# W700B.net
KiCad netlist of a schematic drawn in EAGLE
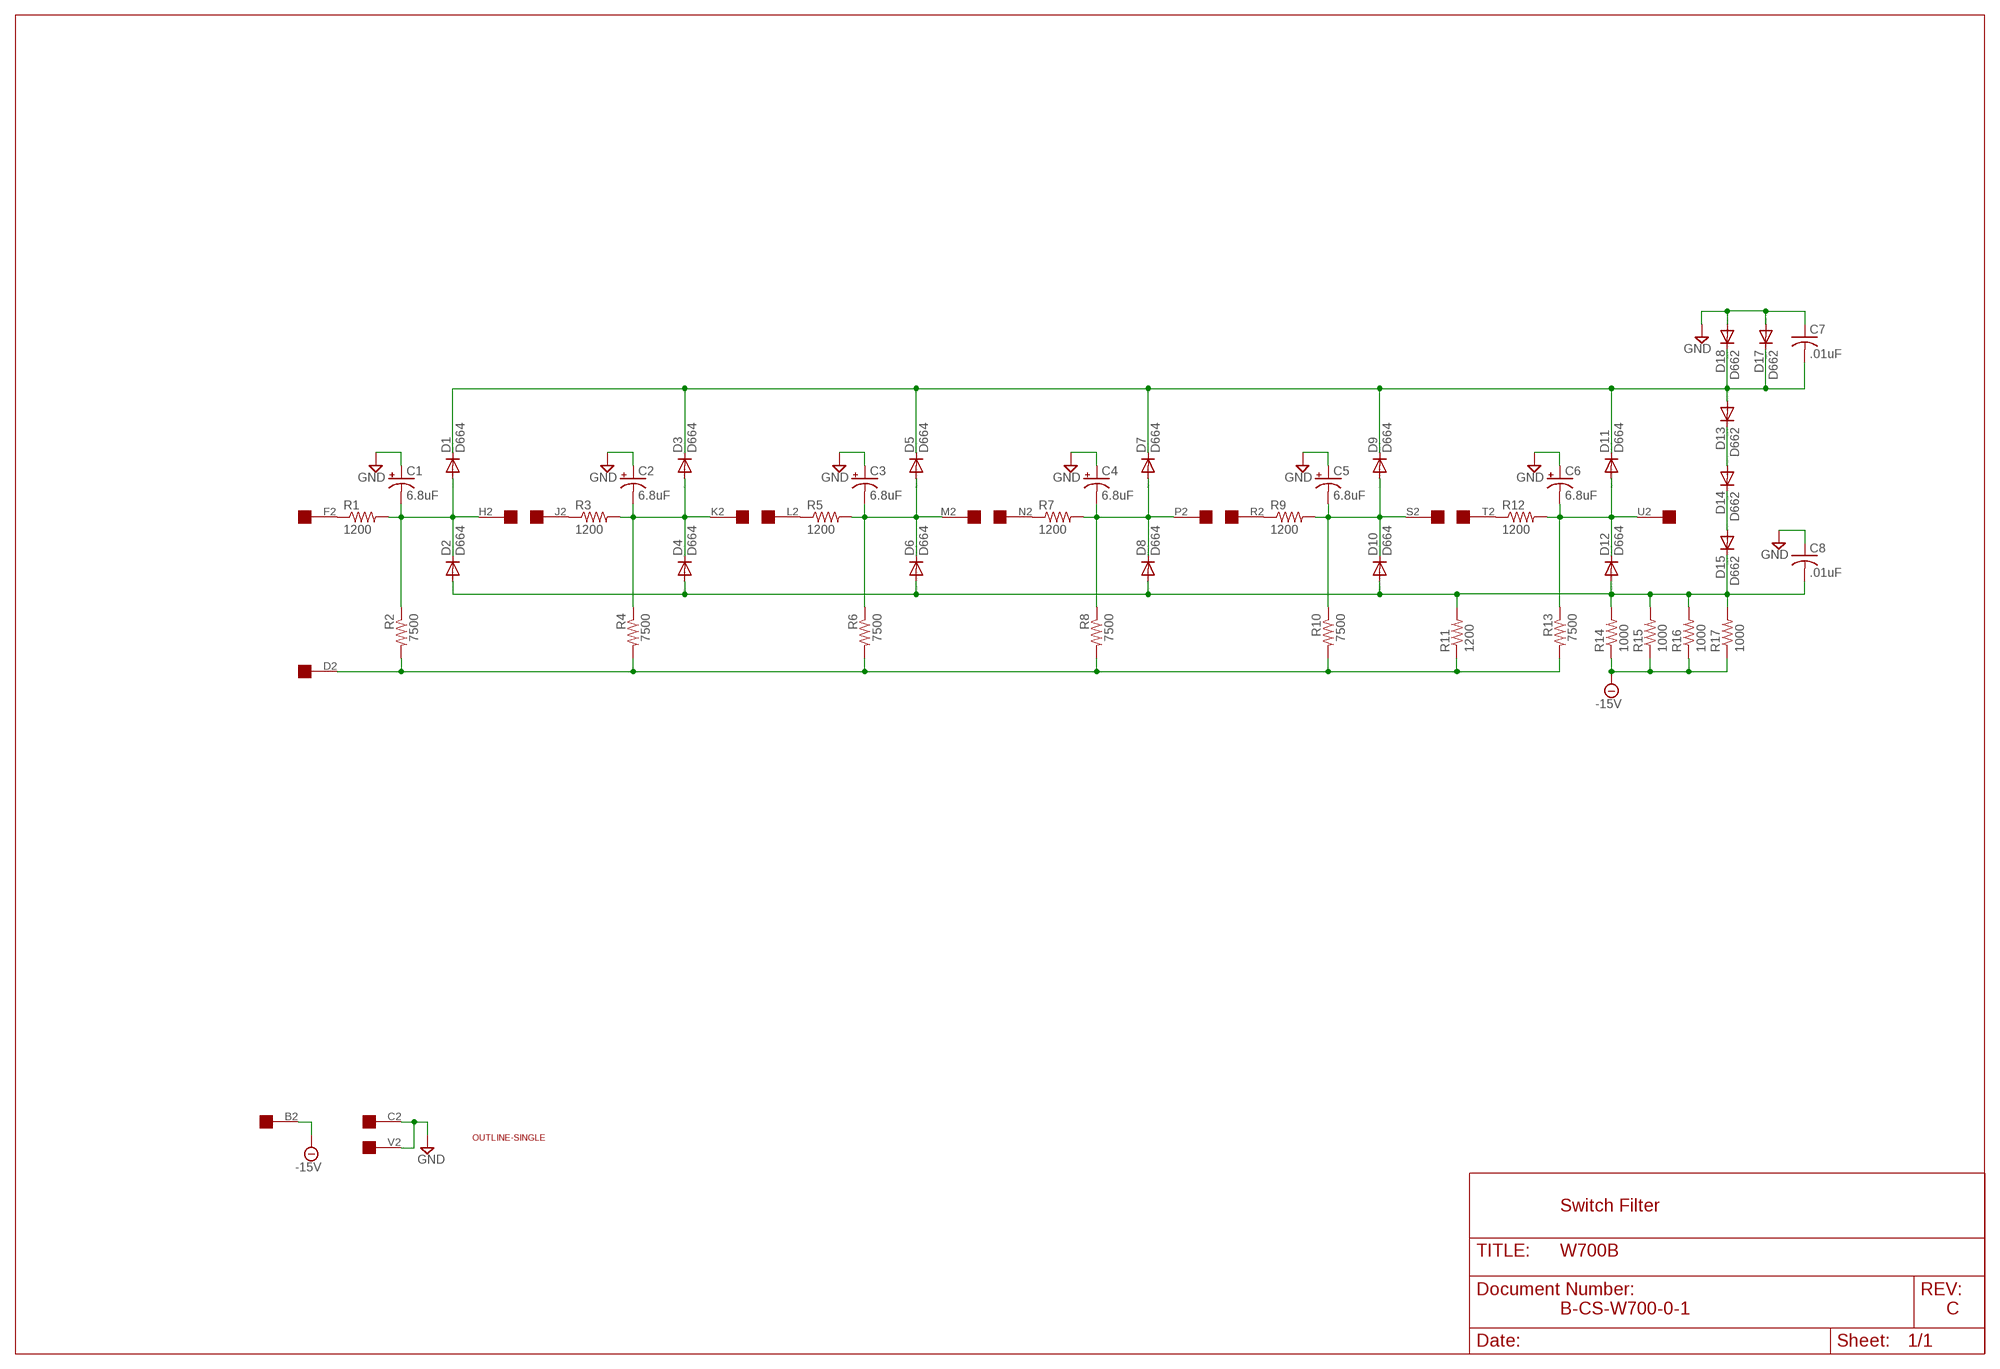
[diagram p0: schematic, sheet 1]

(export (version "E")
  (design (tool "Eeschema 10.0.6"))
  (components
    (comp (ref "C1")
      (value "6.8uF")
      (footprint "eagle-import:E12-8")
      (libsource (lib "eagle-import") (part "CPOL-USE20-8AXIAL"))
    )
    (comp (ref "C2")
      (value "6.8uF")
      (footprint "eagle-import:E12-8")
      (libsource (lib "eagle-import") (part "CPOL-USE20-8AXIAL"))
    )
    (comp (ref "C3")
      (value "6.8uF")
      (footprint "eagle-import:E12-8")
      (libsource (lib "eagle-import") (part "CPOL-USE20-8AXIAL"))
    )
    (comp (ref "C4")
      (value "6.8uF")
      (footprint "eagle-import:E12-8")
      (libsource (lib "eagle-import") (part "CPOL-USE20-8AXIAL"))
    )
    (comp (ref "C5")
      (value "6.8uF")
      (footprint "eagle-import:E12-8")
      (libsource (lib "eagle-import") (part "CPOL-USE20-8AXIAL"))
    )
    (comp (ref "C6")
      (value "6.8uF")
      (footprint "eagle-import:E12-8")
      (libsource (lib "eagle-import") (part "CPOL-USE20-8AXIAL"))
    )
    (comp (ref "C7")
      (value ".01uF")
      (footprint "eagle-import:C150-054X183")
      (libsource (lib "eagle-import") (part "C-US150-054X183"))
    )
    (comp (ref "C8")
      (value ".01uF")
      (footprint "eagle-import:C150-054X183")
      (libsource (lib "eagle-import") (part "C-US150-054X183"))
    )
    (comp (ref "D1")
      (value "D664")
      (footprint "eagle-import:DO35-10")
      (libsource (lib "eagle-import") (part "DIODE-DO35-10"))
    )
    (comp (ref "D2")
      (value "D664")
      (footprint "eagle-import:DO35-10")
      (libsource (lib "eagle-import") (part "DIODE-DO35-10"))
    )
    (comp (ref "D3")
      (value "D664")
      (footprint "eagle-import:DO35-10")
      (libsource (lib "eagle-import") (part "DIODE-DO35-10"))
    )
    (comp (ref "D4")
      (value "D664")
      (footprint "eagle-import:DO35-10")
      (libsource (lib "eagle-import") (part "DIODE-DO35-10"))
    )
    (comp (ref "D5")
      (value "D664")
      (footprint "eagle-import:DO35-10")
      (libsource (lib "eagle-import") (part "DIODE-DO35-10"))
    )
    (comp (ref "D6")
      (value "D664")
      (footprint "eagle-import:DO35-10")
      (libsource (lib "eagle-import") (part "DIODE-DO35-10"))
    )
    (comp (ref "D7")
      (value "D664")
      (footprint "eagle-import:DO35-10")
      (libsource (lib "eagle-import") (part "DIODE-DO35-10"))
    )
    (comp (ref "D8")
      (value "D664")
      (footprint "eagle-import:DO35-10")
      (libsource (lib "eagle-import") (part "DIODE-DO35-10"))
    )
    (comp (ref "D9")
      (value "D664")
      (footprint "eagle-import:DO35-10")
      (libsource (lib "eagle-import") (part "DIODE-DO35-10"))
    )
    (comp (ref "D10")
      (value "D664")
      (footprint "eagle-import:DO35-10")
      (libsource (lib "eagle-import") (part "DIODE-DO35-10"))
    )
    (comp (ref "D11")
      (value "D664")
      (footprint "eagle-import:DO35-10")
      (libsource (lib "eagle-import") (part "DIODE-DO35-10"))
    )
    (comp (ref "D12")
      (value "D664")
      (footprint "eagle-import:DO35-10")
      (libsource (lib "eagle-import") (part "DIODE-DO35-10"))
    )
    (comp (ref "D13")
      (value "D662")
      (footprint "eagle-import:DO35-10")
      (libsource (lib "eagle-import") (part "DIODE-DO35-10"))
    )
    (comp (ref "D14")
      (value "D662")
      (footprint "eagle-import:DO35-10")
      (libsource (lib "eagle-import") (part "DIODE-DO35-10"))
    )
    (comp (ref "D15")
      (value "D662")
      (footprint "eagle-import:DO35-10")
      (libsource (lib "eagle-import") (part "DIODE-DO35-10"))
    )
    (comp (ref "D17")
      (value "D662")
      (footprint "eagle-import:DO35-10")
      (libsource (lib "eagle-import") (part "DIODE-DO35-10"))
    )
    (comp (ref "D18")
      (value "D662")
      (footprint "eagle-import:DO35-10")
      (libsource (lib "eagle-import") (part "DIODE-DO35-10"))
    )
    (comp (ref "R1")
      (value "1200")
      (footprint "eagle-import:0207_10")
      (libsource (lib "eagle-import") (part "R-US_0207/10"))
    )
    (comp (ref "R2")
      (value "7500")
      (footprint "eagle-import:0207_10")
      (libsource (lib "eagle-import") (part "R-US_0207/10"))
    )
    (comp (ref "R3")
      (value "1200")
      (footprint "eagle-import:0207_10")
      (libsource (lib "eagle-import") (part "R-US_0207/10"))
    )
    (comp (ref "R4")
      (value "7500")
      (footprint "eagle-import:0207_10")
      (libsource (lib "eagle-import") (part "R-US_0207/10"))
    )
    (comp (ref "R5")
      (value "1200")
      (footprint "eagle-import:0207_10")
      (libsource (lib "eagle-import") (part "R-US_0207/10"))
    )
    (comp (ref "R6")
      (value "7500")
      (footprint "eagle-import:0207_10")
      (libsource (lib "eagle-import") (part "R-US_0207/10"))
    )
    (comp (ref "R7")
      (value "1200")
      (footprint "eagle-import:0207_10")
      (libsource (lib "eagle-import") (part "R-US_0207/10"))
    )
    (comp (ref "R8")
      (value "7500")
      (footprint "eagle-import:0207_10")
      (libsource (lib "eagle-import") (part "R-US_0207/10"))
    )
    (comp (ref "R9")
      (value "1200")
      (footprint "eagle-import:0207_10")
      (libsource (lib "eagle-import") (part "R-US_0207/10"))
    )
    (comp (ref "R10")
      (value "7500")
      (footprint "eagle-import:0207_10")
      (libsource (lib "eagle-import") (part "R-US_0207/10"))
    )
    (comp (ref "R11")
      (value "1200")
      (footprint "eagle-import:0207_10")
      (libsource (lib "eagle-import") (part "R-US_0207/10"))
    )
    (comp (ref "R12")
      (value "1200")
      (footprint "eagle-import:0207_10")
      (libsource (lib "eagle-import") (part "R-US_0207/10"))
    )
    (comp (ref "R13")
      (value "7500")
      (footprint "eagle-import:0207_10")
      (libsource (lib "eagle-import") (part "R-US_0207/10"))
    )
    (comp (ref "R14")
      (value "1000")
      (footprint "eagle-import:0207_10")
      (libsource (lib "eagle-import") (part "R-US_0207/10"))
    )
    (comp (ref "R15")
      (value "1000")
      (footprint "eagle-import:0207_10")
      (libsource (lib "eagle-import") (part "R-US_0207/10"))
    )
    (comp (ref "R16")
      (value "1000")
      (footprint "eagle-import:0207_10")
      (libsource (lib "eagle-import") (part "R-US_0207/10"))
    )
    (comp (ref "R17")
      (value "1000")
      (footprint "eagle-import:0207_10")
      (libsource (lib "eagle-import") (part "R-US_0207/10"))
    )
    (comp (ref "U$1")
      (value "OUTLINE-SINGLE")
      (footprint "eagle-import:SINGLE")
      (libsource (lib "eagle-import") (part "OUTLINE-SINGLE"))
    )
    (comp (ref "U$3")
      (value "EDGE-1")
      (footprint "eagle-import:EDGE-CON1")
      (libsource (lib "eagle-import") (part "EDGE-1"))
    )
  )
  (nets
    (net (code "1") (name "-15V") (class "Default")
      (node (ref "R14") (pin "1") (pinfunction "1_1") (pintype "passive"))
      (node (ref "R15") (pin "1") (pinfunction "1_1") (pintype "passive"))
      (node (ref "R16") (pin "1") (pinfunction "1_1") (pintype "passive"))
      (node (ref "R17") (pin "1") (pinfunction "1_1") (pintype "passive"))
      (node (ref "U$3") (pin "B2") (pinfunction "1_B2") (pintype "bidirectional"))
    )
    (net (code "2") (name "GND") (class "Default")
      (node (ref "C1") (pin "+") (pinfunction "+_+") (pintype "passive"))
      (node (ref "C2") (pin "+") (pinfunction "+_+") (pintype "passive"))
      (node (ref "C3") (pin "+") (pinfunction "+_+") (pintype "passive"))
      (node (ref "C4") (pin "+") (pinfunction "+_+") (pintype "passive"))
      (node (ref "C5") (pin "+") (pinfunction "+_+") (pintype "passive"))
      (node (ref "C6") (pin "+") (pinfunction "+_+") (pintype "passive"))
      (node (ref "C7") (pin "1") (pinfunction "1_1") (pintype "passive"))
      (node (ref "C8") (pin "1") (pinfunction "1_1") (pintype "passive"))
      (node (ref "D17") (pin "A") (pinfunction "A_A") (pintype "passive"))
      (node (ref "D18") (pin "A") (pinfunction "A_A") (pintype "passive"))
      (node (ref "U$3") (pin "C2") (pinfunction "1_C2") (pintype "bidirectional"))
      (node (ref "U$3") (pin "V2") (pinfunction "1_V2") (pintype "bidirectional"))
    )
    (net (code "3") (name "Net-(C7-Pad2)") (class "Default")
      (node (ref "C7") (pin "2") (pinfunction "2_2") (pintype "passive"))
      (node (ref "D1") (pin "C") (pinfunction "C_C") (pintype "passive"))
      (node (ref "D11") (pin "C") (pinfunction "C_C") (pintype "passive"))
      (node (ref "D13") (pin "A") (pinfunction "A_A") (pintype "passive"))
      (node (ref "D17") (pin "C") (pinfunction "C_C") (pintype "passive"))
      (node (ref "D18") (pin "C") (pinfunction "C_C") (pintype "passive"))
      (node (ref "D3") (pin "C") (pinfunction "C_C") (pintype "passive"))
      (node (ref "D5") (pin "C") (pinfunction "C_C") (pintype "passive"))
      (node (ref "D7") (pin "C") (pinfunction "C_C") (pintype "passive"))
      (node (ref "D9") (pin "C") (pinfunction "C_C") (pintype "passive"))
    )
    (net (code "4") (name "Net-(C8-Pad2)") (class "Default")
      (node (ref "C8") (pin "2") (pinfunction "2_2") (pintype "passive"))
      (node (ref "D10") (pin "A") (pinfunction "A_A") (pintype "passive"))
      (node (ref "D12") (pin "A") (pinfunction "A_A") (pintype "passive"))
      (node (ref "D15") (pin "C") (pinfunction "C_C") (pintype "passive"))
      (node (ref "D2") (pin "A") (pinfunction "A_A") (pintype "passive"))
      (node (ref "D4") (pin "A") (pinfunction "A_A") (pintype "passive"))
      (node (ref "D6") (pin "A") (pinfunction "A_A") (pintype "passive"))
      (node (ref "D8") (pin "A") (pinfunction "A_A") (pintype "passive"))
      (node (ref "R11") (pin "2") (pinfunction "2_2") (pintype "passive"))
      (node (ref "R14") (pin "2") (pinfunction "2_2") (pintype "passive"))
      (node (ref "R15") (pin "2") (pinfunction "2_2") (pintype "passive"))
      (node (ref "R16") (pin "2") (pinfunction "2_2") (pintype "passive"))
      (node (ref "R17") (pin "2") (pinfunction "2_2") (pintype "passive"))
    )
    (net (code "5") (name "Net-(D13-PadC)") (class "Default")
      (node (ref "D13") (pin "C") (pinfunction "C_C") (pintype "passive"))
      (node (ref "D14") (pin "A") (pinfunction "A_A") (pintype "passive"))
    )
    (net (code "6") (name "Net-(D14-PadC)") (class "Default")
      (node (ref "D14") (pin "C") (pinfunction "C_C") (pintype "passive"))
      (node (ref "D15") (pin "A") (pinfunction "A_A") (pintype "passive"))
    )
    (net (code "7") (name "Net-(U$3D-1)") (class "Default")
      (node (ref "R10") (pin "2") (pinfunction "2_2") (pintype "passive"))
      (node (ref "R11") (pin "1") (pinfunction "1_1") (pintype "passive"))
      (node (ref "R13") (pin "2") (pinfunction "2_2") (pintype "passive"))
      (node (ref "R2") (pin "2") (pinfunction "2_2") (pintype "passive"))
      (node (ref "R4") (pin "2") (pinfunction "2_2") (pintype "passive"))
      (node (ref "R6") (pin "2") (pinfunction "2_2") (pintype "passive"))
      (node (ref "R8") (pin "2") (pinfunction "2_2") (pintype "passive"))
      (node (ref "U$3") (pin "D2") (pinfunction "1_D2") (pintype "bidirectional"))
    )
    (net (code "8") (name "Net-(U$3F-1)") (class "Default")
      (node (ref "R1") (pin "1") (pinfunction "1_1") (pintype "passive"))
      (node (ref "U$3") (pin "F2") (pinfunction "1_F2") (pintype "bidirectional"))
    )
    (net (code "9") (name "Net-(U$3G-1)") (class "Default")
      (node (ref "C1") (pin "-") (pinfunction "-_-") (pintype "passive"))
      (node (ref "D1") (pin "A") (pinfunction "A_A") (pintype "passive"))
      (node (ref "D2") (pin "C") (pinfunction "C_C") (pintype "passive"))
      (node (ref "R1") (pin "2") (pinfunction "2_2") (pintype "passive"))
      (node (ref "R2") (pin "1") (pinfunction "1_1") (pintype "passive"))
      (node (ref "U$3") (pin "H2") (pinfunction "1_H2") (pintype "bidirectional"))
    )
    (net (code "10") (name "Net-(U$3H-1)") (class "Default")
      (node (ref "R3") (pin "1") (pinfunction "1_1") (pintype "passive"))
      (node (ref "U$3") (pin "J2") (pinfunction "1_J2") (pintype "bidirectional"))
    )
    (net (code "11") (name "Net-(U$3I-1)") (class "Default")
      (node (ref "C2") (pin "-") (pinfunction "-_-") (pintype "passive"))
      (node (ref "D3") (pin "A") (pinfunction "A_A") (pintype "passive"))
      (node (ref "D4") (pin "C") (pinfunction "C_C") (pintype "passive"))
      (node (ref "R3") (pin "2") (pinfunction "2_2") (pintype "passive"))
      (node (ref "R4") (pin "1") (pinfunction "1_1") (pintype "passive"))
      (node (ref "U$3") (pin "K2") (pinfunction "1_K2") (pintype "bidirectional"))
    )
    (net (code "12") (name "Net-(U$3J-1)") (class "Default")
      (node (ref "R5") (pin "1") (pinfunction "1_1") (pintype "passive"))
      (node (ref "U$3") (pin "L2") (pinfunction "1_L2") (pintype "bidirectional"))
    )
    (net (code "13") (name "Net-(U$3K-1)") (class "Default")
      (node (ref "C3") (pin "-") (pinfunction "-_-") (pintype "passive"))
      (node (ref "D5") (pin "A") (pinfunction "A_A") (pintype "passive"))
      (node (ref "D6") (pin "C") (pinfunction "C_C") (pintype "passive"))
      (node (ref "R5") (pin "2") (pinfunction "2_2") (pintype "passive"))
      (node (ref "R6") (pin "1") (pinfunction "1_1") (pintype "passive"))
      (node (ref "U$3") (pin "M2") (pinfunction "1_M2") (pintype "bidirectional"))
    )
    (net (code "14") (name "Net-(U$3L-1)") (class "Default")
      (node (ref "R7") (pin "1") (pinfunction "1_1") (pintype "passive"))
      (node (ref "U$3") (pin "N2") (pinfunction "1_N2") (pintype "bidirectional"))
    )
    (net (code "15") (name "Net-(U$3M-1)") (class "Default")
      (node (ref "C4") (pin "-") (pinfunction "-_-") (pintype "passive"))
      (node (ref "D7") (pin "A") (pinfunction "A_A") (pintype "passive"))
      (node (ref "D8") (pin "C") (pinfunction "C_C") (pintype "passive"))
      (node (ref "R7") (pin "2") (pinfunction "2_2") (pintype "passive"))
      (node (ref "R8") (pin "1") (pinfunction "1_1") (pintype "passive"))
      (node (ref "U$3") (pin "P2") (pinfunction "1_P2") (pintype "bidirectional"))
    )
    (net (code "16") (name "Net-(U$3N-1)") (class "Default")
      (node (ref "R9") (pin "1") (pinfunction "1_1") (pintype "passive"))
      (node (ref "U$3") (pin "R2") (pinfunction "1_R2") (pintype "bidirectional"))
    )
    (net (code "17") (name "Net-(U$3O-1)") (class "Default")
      (node (ref "C5") (pin "-") (pinfunction "-_-") (pintype "passive"))
      (node (ref "D10") (pin "C") (pinfunction "C_C") (pintype "passive"))
      (node (ref "D9") (pin "A") (pinfunction "A_A") (pintype "passive"))
      (node (ref "R10") (pin "1") (pinfunction "1_1") (pintype "passive"))
      (node (ref "R9") (pin "2") (pinfunction "2_2") (pintype "passive"))
      (node (ref "U$3") (pin "S2") (pinfunction "1_S2") (pintype "bidirectional"))
    )
    (net (code "18") (name "Net-(U$3P-1)") (class "Default")
      (node (ref "R12") (pin "1") (pinfunction "1_1") (pintype "passive"))
      (node (ref "U$3") (pin "T2") (pinfunction "1_T2") (pintype "bidirectional"))
    )
    (net (code "19") (name "Net-(U$3Q-1)") (class "Default")
      (node (ref "C6") (pin "-") (pinfunction "-_-") (pintype "passive"))
      (node (ref "D11") (pin "A") (pinfunction "A_A") (pintype "passive"))
      (node (ref "D12") (pin "C") (pinfunction "C_C") (pintype "passive"))
      (node (ref "R12") (pin "2") (pinfunction "2_2") (pintype "passive"))
      (node (ref "R13") (pin "1") (pinfunction "1_1") (pintype "passive"))
      (node (ref "U$3") (pin "U2") (pinfunction "1_U2") (pintype "bidirectional"))
    )
  )
)
